# Audio.net
KiCad netlist of a schematic drawn in Altium Designer
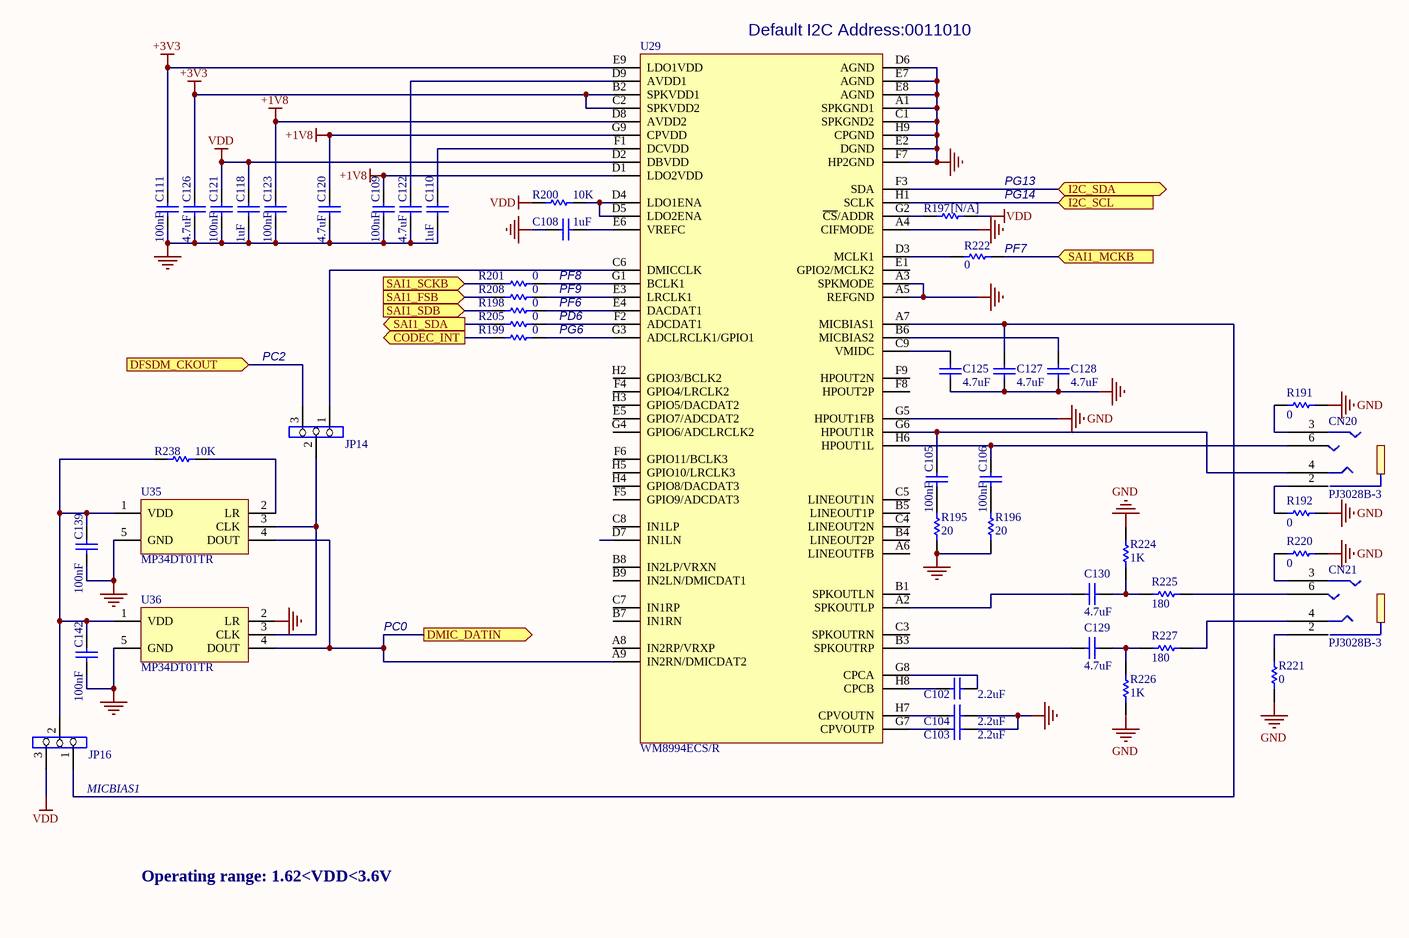
[diagram p0: Audio.SchDoc]

(export (version "E")
  (design (tool "Eeschema 10.0.6"))
  (components
    (comp (ref "C102")
      (value "2.2uF")
      (footprint "0603C")
      (description "Capacitor")
      (fields (field (name "PUBLISHER") "Altium Limited"))
      (libsource (lib "Miscellaneous Devices") (part "CAP"))
    )
    (comp (ref "C103")
      (value "2.2uF")
      (footprint "0603C")
      (description "Capacitor")
      (fields (field (name "PUBLISHER") "Altium Limited"))
      (libsource (lib "Miscellaneous Devices") (part "CAP"))
    )
    (comp (ref "C104")
      (value "2.2uF")
      (footprint "0603C")
      (description "Capacitor")
      (fields (field (name "PUBLISHER") "Altium Limited"))
      (libsource (lib "Miscellaneous Devices") (part "CAP"))
    )
    (comp (ref "C105")
      (value "100nF")
      (footprint "0402C")
      (description "Capacitor")
      (fields (field (name "PUBLISHER") "Altium Limited"))
      (libsource (lib "Miscellaneous Devices") (part "Cap"))
    )
    (comp (ref "C106")
      (value "100nF")
      (footprint "0402C")
      (description "Capacitor")
      (fields (field (name "PUBLISHER") "Altium Limited"))
      (libsource (lib "Miscellaneous Devices") (part "Cap"))
    )
    (comp (ref "C108")
      (value "1uF")
      (footprint "0603C")
      (description "Capacitor")
      (fields (field (name "PUBLISHER") "Altium Limited"))
      (libsource (lib "Miscellaneous Devices") (part "CAP"))
    )
    (comp (ref "C109")
      (value "100nF")
      (footprint "0402C")
      (description "Capacitor")
      (fields (field (name "PUBLISHER") "Altium Limited"))
      (libsource (lib "Miscellaneous Devices") (part "Cap"))
    )
    (comp (ref "C110")
      (value "1uF")
      (footprint "0603C")
      (description "Capacitor")
      (fields (field (name "PUBLISHER") "Altium Limited"))
      (libsource (lib "Miscellaneous Devices") (part "CAP"))
    )
    (comp (ref "C111")
      (value "100nF")
      (footprint "0402C")
      (description "Capacitor")
      (fields (field (name "PUBLISHER") "Altium Limited"))
      (libsource (lib "Miscellaneous Devices") (part "Cap"))
    )
    (comp (ref "C118")
      (value "1uF")
      (footprint "0603C")
      (description "Capacitor")
      (fields (field (name "PUBLISHER") "Altium Limited"))
      (libsource (lib "Miscellaneous Devices") (part "CAP"))
    )
    (comp (ref "C120")
      (value "4.7uF")
      (footprint "0603C")
      (description "Capacitor")
      (fields (field (name "PUBLISHER") "Altium Limited"))
      (libsource (lib "Miscellaneous Devices") (part "Cap"))
    )
    (comp (ref "C121")
      (value "100nF")
      (footprint "0402C")
      (description "Capacitor")
      (fields (field (name "PUBLISHER") "Altium Limited"))
      (libsource (lib "Miscellaneous Devices") (part "Cap"))
    )
    (comp (ref "C122")
      (value "4.7uF")
      (footprint "0603C")
      (description "Capacitor")
      (fields (field (name "PUBLISHER") "Altium Limited"))
      (libsource (lib "Miscellaneous Devices") (part "Cap"))
    )
    (comp (ref "C123")
      (value "100nF")
      (footprint "0402C")
      (description "Capacitor")
      (fields (field (name "PUBLISHER") "Altium Limited"))
      (libsource (lib "Miscellaneous Devices") (part "Cap"))
    )
    (comp (ref "C125")
      (value "4.7uF")
      (footprint "0603C")
      (description "Capacitor")
      (fields (field (name "PUBLISHER") "Altium Limited"))
      (libsource (lib "Miscellaneous Devices") (part "Cap"))
    )
    (comp (ref "C126")
      (value "4.7uF")
      (footprint "0603C")
      (description "Capacitor")
      (fields (field (name "PUBLISHER") "Altium Limited"))
      (libsource (lib "Miscellaneous Devices") (part "Cap"))
    )
    (comp (ref "C127")
      (value "4.7uF")
      (footprint "0603C")
      (description "Capacitor")
      (fields (field (name "PUBLISHER") "Altium Limited"))
      (libsource (lib "Miscellaneous Devices") (part "Cap"))
    )
    (comp (ref "C128")
      (value "4.7uF")
      (footprint "0603C")
      (description "Capacitor")
      (fields (field (name "PUBLISHER") "Altium Limited"))
      (libsource (lib "Miscellaneous Devices") (part "Cap"))
    )
    (comp (ref "C129")
      (value "4.7uF")
      (footprint "0603C")
      (description "Capacitor")
      (fields (field (name "PUBLISHER") "Altium Limited"))
      (libsource (lib "Miscellaneous Devices") (part "Cap"))
    )
    (comp (ref "C130")
      (value "4.7uF")
      (footprint "0603C")
      (description "Capacitor")
      (fields (field (name "PUBLISHER") "Altium Limited"))
      (libsource (lib "Miscellaneous Devices") (part "Cap"))
    )
    (comp (ref "C139")
      (value "100nF")
      (footprint "0402C")
      (description "Capacitor")
      (fields (field (name "PUBLISHER") "Altium Limited"))
      (libsource (lib "Miscellaneous Devices") (part "Cap"))
    )
    (comp (ref "C142")
      (value "100nF")
      (footprint "0402C")
      (description "Capacitor")
      (fields (field (name "PUBLISHER") "Altium Limited"))
      (libsource (lib "Miscellaneous Devices") (part "Cap"))
    )
    (comp (ref "CN20") (value "PJ3028B-3") (footprint "PJ3028B") (libsource (lib "MB786") (part "PJ3028B-3")))
    (comp (ref "CN21") (value "PJ3028B-3") (footprint "PJ3028B") (libsource (lib "MB786") (part "PJ3028B-3")))
    (comp (ref "JP14")
      (value "Header 3X1")
      (footprint "SIP3")
      (libsource (lib "STR910_SCHLIB") (part "Jumper3"))
    )
    (comp (ref "JP16")
      (value "Header 3X1")
      (footprint "SIP3")
      (libsource (lib "STR910_SCHLIB") (part "Jumper3"))
    )
    (comp (ref "R191")
      (value "0")
      (footprint "0603R")
      (description "Resistor")
      (fields (field (name "PUBLISHER") "Altium Limited"))
      (libsource (lib "Miscellaneous Devices") (part "Res1"))
    )
    (comp (ref "R192")
      (value "0")
      (footprint "0603R")
      (description "Resistor")
      (fields (field (name "PUBLISHER") "Altium Limited"))
      (libsource (lib "Miscellaneous Devices") (part "Res1"))
    )
    (comp (ref "R195")
      (value "20")
      (footprint "0402R")
      (description "Resistor")
      (fields (field (name "PUBLISHER") "Altium Limited"))
      (libsource (lib "Miscellaneous Devices") (part "Res1"))
    )
    (comp (ref "R196")
      (value "20")
      (footprint "0402R")
      (description "Resistor")
      (fields (field (name "PUBLISHER") "Altium Limited"))
      (libsource (lib "Miscellaneous Devices") (part "Res1"))
    )
    (comp (ref "R197")
      (value "[N/A]")
      (footprint "0603R")
      (description "Resistor")
      (fields (field (name "PUBLISHER") "Altium Limited"))
      (libsource (lib "Miscellaneous Devices") (part "Res1"))
    )
    (comp (ref "R198")
      (value "0")
      (footprint "0603R")
      (description "Resistor")
      (fields (field (name "PUBLISHER") "Altium Limited"))
      (libsource (lib "Miscellaneous Devices") (part "Res1"))
    )
    (comp (ref "R199")
      (value "0")
      (footprint "0603R")
      (description "Resistor")
      (fields (field (name "PUBLISHER") "Altium Limited"))
      (libsource (lib "Miscellaneous Devices") (part "Res1"))
    )
    (comp (ref "R200")
      (value "10K")
      (footprint "0402R")
      (description "Resistor")
      (fields (field (name "PUBLISHER") "Altium Limited"))
      (libsource (lib "Miscellaneous Devices") (part "Res1"))
    )
    (comp (ref "R201")
      (value "0")
      (footprint "0603R")
      (description "Resistor")
      (fields (field (name "PUBLISHER") "Altium Limited"))
      (libsource (lib "Miscellaneous Devices") (part "Res1"))
    )
    (comp (ref "R205")
      (value "0")
      (footprint "0603R")
      (description "Resistor")
      (fields (field (name "PUBLISHER") "Altium Limited"))
      (libsource (lib "Miscellaneous Devices") (part "Res1"))
    )
    (comp (ref "R208")
      (value "0")
      (footprint "0603R")
      (description "Resistor")
      (fields (field (name "PUBLISHER") "Altium Limited"))
      (libsource (lib "Miscellaneous Devices") (part "Res1"))
    )
    (comp (ref "R220")
      (value "0")
      (footprint "0603R")
      (description "Resistor")
      (fields (field (name "PUBLISHER") "Altium Limited"))
      (libsource (lib "Miscellaneous Devices") (part "Res1"))
    )
    (comp (ref "R221")
      (value "0")
      (footprint "0603R")
      (description "Resistor")
      (fields (field (name "PUBLISHER") "Altium Limited"))
      (libsource (lib "Miscellaneous Devices") (part "Res1"))
    )
    (comp (ref "R222")
      (value "0")
      (footprint "0603R")
      (description "Resistor")
      (fields (field (name "PUBLISHER") "Altium Limited"))
      (libsource (lib "Miscellaneous Devices") (part "Res1"))
    )
    (comp (ref "R224")
      (value "1K")
      (footprint "0402R")
      (description "Resistor")
      (fields (field (name "PUBLISHER") "Altium Limited"))
      (libsource (lib "Miscellaneous Devices") (part "Res1"))
    )
    (comp (ref "R225")
      (value "180")
      (footprint "0402R")
      (description "Resistor")
      (fields (field (name "PUBLISHER") "Altium Limited"))
      (libsource (lib "Miscellaneous Devices") (part "Res1"))
    )
    (comp (ref "R226")
      (value "1K")
      (footprint "0402R")
      (description "Resistor")
      (fields (field (name "PUBLISHER") "Altium Limited"))
      (libsource (lib "Miscellaneous Devices") (part "Res1"))
    )
    (comp (ref "R227")
      (value "180")
      (footprint "0402R")
      (description "Resistor")
      (fields (field (name "PUBLISHER") "Altium Limited"))
      (libsource (lib "Miscellaneous Devices") (part "Res1"))
    )
    (comp (ref "R238")
      (value "10K")
      (footprint "0402R")
      (description "Resistor")
      (fields (field (name "PUBLISHER") "Altium Limited"))
      (libsource (lib "Miscellaneous Devices") (part "Res1"))
    )
    (comp (ref "U29")
      (value "WM8994ECS/R")
      (footprint "BGA72_0R5_4R5X4")
      (libsource (lib "mb1045") (part "WM8994ECS/R"))
    )
    (comp (ref "U35")
      (value "MP34DT01TR")
      (footprint "MP34DT01TR")
      (description "MEMS audio sensor")
      (fields (field (name "PUBLISHER") "Altium Limited"))
      (libsource (lib "mb1045") (part "MP34DT01TR"))
    )
    (comp (ref "U36")
      (value "MP34DT01TR")
      (footprint "MP34DT01TR")
      (description "MEMS audio sensor")
      (fields (field (name "PUBLISHER") "Altium Limited"))
      (libsource (lib "mb1045") (part "MP34DT01TR"))
    )
  )
  (nets
    (net (code "1") (name "+1V8") (class "Default")
      (node (ref "C109") (pin "1") (pinfunction "1_1") (pintype "passive"))
      (node (ref "C120") (pin "1") (pinfunction "1_1") (pintype "passive"))
      (node (ref "C123") (pin "1") (pinfunction "1_1") (pintype "passive"))
      (node (ref "U29") (pin "D1") (pinfunction "LDO2VDD_D1") (pintype "passive"))
      (node (ref "U29") (pin "D8") (pinfunction "AVDD2_D8") (pintype "passive"))
      (node (ref "U29") (pin "G9") (pinfunction "CPVDD_G9") (pintype "passive"))
    )
    (net (code "2") (name "+3V3") (class "Default")
      (node (ref "C111") (pin "1") (pinfunction "1_1") (pintype "passive"))
      (node (ref "C126") (pin "1") (pinfunction "1_1") (pintype "passive"))
      (node (ref "U29") (pin "B2") (pinfunction "SPKVDD1_B2") (pintype "passive"))
      (node (ref "U29") (pin "C2") (pinfunction "SPKVDD2_C2") (pintype "passive"))
      (node (ref "U29") (pin "E9") (pinfunction "LDO1VDD_E9") (pintype "passive"))
    )
    (net (code "3") (name "/CODEC_INT") (class "Default")
      (node (ref "R199") (pin "2") (pinfunction "2_2") (pintype "passive"))
    )
    (net (code "4") (name "/DFSDM_CKOUT") (class "Default") (node (ref "JP14") (pin "3") (pintype "passive")))
    (net (code "5") (name "/DMIC_DATIN") (class "Default")
      (node (ref "U29") (pin "A9") (pinfunction "IN2RN/DMICDAT2_A9") (pintype "passive"))
      (node (ref "U35") (pin "4") (pinfunction "DOUT_4") (pintype "passive"))
      (node (ref "U36") (pin "4") (pinfunction "DOUT_4") (pintype "passive"))
    )
    (net (code "6") (name "/I2C_SCL") (class "Default")
      (node (ref "U29") (pin "H1") (pinfunction "SCLK_H1") (pintype "passive"))
    )
    (net (code "7") (name "/I2C_SDA") (class "Default")
      (node (ref "U29") (pin "F3") (pinfunction "SDA_F3") (pintype "passive"))
    )
    (net (code "8") (name "/SAI1_FSB") (class "Default")
      (node (ref "R208") (pin "2") (pinfunction "2_2") (pintype "passive"))
    )
    (net (code "9") (name "/SAI1_MCKB") (class "Default")
      (node (ref "R222") (pin "1") (pinfunction "1_1") (pintype "passive"))
    )
    (net (code "10") (name "/SAI1_SCKB") (class "Default")
      (node (ref "R201") (pin "2") (pinfunction "2_2") (pintype "passive"))
    )
    (net (code "11") (name "/SAI1_SDA") (class "Default")
      (node (ref "R205") (pin "2") (pinfunction "2_2") (pintype "passive"))
    )
    (net (code "12") (name "/SAI1_SDB") (class "Default")
      (node (ref "R198") (pin "2") (pinfunction "2_2") (pintype "passive"))
    )
    (net (code "13") (name "GND") (class "Default")
      (node (ref "C103") (pin "2") (pinfunction "2_2") (pintype "passive"))
      (node (ref "C104") (pin "2") (pinfunction "2_2") (pintype "passive"))
      (node (ref "C108") (pin "2") (pinfunction "2_2") (pintype "passive"))
      (node (ref "C109") (pin "2") (pinfunction "2_2") (pintype "passive"))
      (node (ref "C110") (pin "2") (pinfunction "2_2") (pintype "passive"))
      (node (ref "C111") (pin "2") (pinfunction "2_2") (pintype "passive"))
      (node (ref "C118") (pin "2") (pinfunction "2_2") (pintype "passive"))
      (node (ref "C120") (pin "2") (pinfunction "2_2") (pintype "passive"))
      (node (ref "C121") (pin "2") (pinfunction "2_2") (pintype "passive"))
      (node (ref "C122") (pin "2") (pinfunction "2_2") (pintype "passive"))
      (node (ref "C123") (pin "2") (pinfunction "2_2") (pintype "passive"))
      (node (ref "C125") (pin "1") (pinfunction "1_1") (pintype "passive"))
      (node (ref "C126") (pin "2") (pinfunction "2_2") (pintype "passive"))
      (node (ref "C127") (pin "1") (pinfunction "1_1") (pintype "passive"))
      (node (ref "C128") (pin "1") (pinfunction "1_1") (pintype "passive"))
      (node (ref "C139") (pin "2") (pinfunction "2_2") (pintype "passive"))
      (node (ref "C142") (pin "2") (pinfunction "2_2") (pintype "passive"))
      (node (ref "R191") (pin "2") (pinfunction "2_2") (pintype "passive"))
      (node (ref "R192") (pin "1") (pinfunction "1_1") (pintype "passive"))
      (node (ref "R195") (pin "2") (pinfunction "2_2") (pintype "passive"))
      (node (ref "R196") (pin "2") (pinfunction "2_2") (pintype "passive"))
      (node (ref "R220") (pin "2") (pinfunction "2_2") (pintype "passive"))
      (node (ref "R221") (pin "2") (pinfunction "2_2") (pintype "passive"))
      (node (ref "R224") (pin "1") (pinfunction "1_1") (pintype "passive"))
      (node (ref "R226") (pin "1") (pinfunction "1_1") (pintype "passive"))
      (node (ref "U29") (pin "A1") (pinfunction "SPKGND1_A1") (pintype "passive"))
      (node (ref "U29") (pin "A3") (pinfunction "SPKMODE_A3") (pintype "passive"))
      (node (ref "U29") (pin "A4") (pinfunction "CIFMODE_A4") (pintype "passive"))
      (node (ref "U29") (pin "A5") (pinfunction "REFGND_A5") (pintype "passive"))
      (node (ref "U29") (pin "C1") (pinfunction "SPKGND2_C1") (pintype "passive"))
      (node (ref "U29") (pin "D6") (pinfunction "AGND_D6") (pintype "passive"))
      (node (ref "U29") (pin "E2") (pinfunction "DGND_E2") (pintype "passive"))
      (node (ref "U29") (pin "E7") (pinfunction "AGND_E7") (pintype "passive"))
      (node (ref "U29") (pin "E8") (pinfunction "AGND_E8") (pintype "passive"))
      (node (ref "U29") (pin "F7") (pinfunction "HP2GND_F7") (pintype "passive"))
      (node (ref "U29") (pin "G5") (pinfunction "HPOUT1FB_G5") (pintype "passive"))
      (node (ref "U29") (pin "H9") (pinfunction "CPGND_H9") (pintype "passive"))
      (node (ref "U35") (pin "5") (pinfunction "GND_5") (pintype "passive"))
      (node (ref "U36") (pin "2") (pinfunction "LR_2") (pintype "passive"))
      (node (ref "U36") (pin "5") (pinfunction "GND_5") (pintype "passive"))
    )
    (net (code "14") (name "Net-(C105-Pad2)") (class "Default")
      (node (ref "C105") (pin "2") (pinfunction "2_2") (pintype "passive"))
      (node (ref "R195") (pin "1") (pinfunction "1_1") (pintype "passive"))
    )
    (net (code "15") (name "Net-(C106-Pad2)") (class "Default")
      (node (ref "C106") (pin "2") (pinfunction "2_2") (pintype "passive"))
      (node (ref "R196") (pin "1") (pinfunction "1_1") (pintype "passive"))
    )
    (net (code "16") (name "Net-(C129-Pad1)") (class "Default")
      (node (ref "C129") (pin "1") (pinfunction "1_1") (pintype "passive"))
      (node (ref "R226") (pin "2") (pinfunction "2_2") (pintype "passive"))
      (node (ref "R227") (pin "2") (pinfunction "2_2") (pintype "passive"))
    )
    (net (code "17") (name "Net-(C130-Pad1)") (class "Default")
      (node (ref "C130") (pin "1") (pinfunction "1_1") (pintype "passive"))
      (node (ref "R224") (pin "2") (pinfunction "2_2") (pintype "passive"))
      (node (ref "R225") (pin "1") (pinfunction "1_1") (pintype "passive"))
    )
    (net (code "18") (name "Net-(CN20-Pad2)") (class "Default")
      (node (ref "CN20") (pin "2") (pintype "passive"))
      (node (ref "R192") (pin "2") (pinfunction "2_2") (pintype "passive"))
    )
    (net (code "19") (name "Net-(CN20-Pad3)") (class "Default")
      (node (ref "CN20") (pin "3") (pintype "passive"))
      (node (ref "R191") (pin "1") (pinfunction "1_1") (pintype "passive"))
    )
    (net (code "20") (name "Net-(CN21-Pad2)") (class "Default")
      (node (ref "CN21") (pin "2") (pintype "passive"))
      (node (ref "R221") (pin "1") (pinfunction "1_1") (pintype "passive"))
    )
    (net (code "21") (name "Net-(CN21-Pad3)") (class "Default")
      (node (ref "CN21") (pin "3") (pintype "passive"))
      (node (ref "R220") (pin "1") (pinfunction "1_1") (pintype "passive"))
    )
    (net (code "22") (name "Net-(CN21-Pad4)") (class "Default")
      (node (ref "CN21") (pin "4") (pintype "passive"))
      (node (ref "R227") (pin "1") (pinfunction "1_1") (pintype "passive"))
    )
    (net (code "23") (name "Net-(CN21-Pad6)") (class "Default")
      (node (ref "CN21") (pin "6") (pintype "passive"))
      (node (ref "R225") (pin "2") (pinfunction "2_2") (pintype "passive"))
    )
    (net (code "24") (name "Net-(U29-ADCDAT1)") (class "Default")
      (node (ref "R205") (pin "1") (pinfunction "1_1") (pintype "passive"))
      (node (ref "U29") (pin "F2") (pinfunction "ADCDAT1_F2") (pintype "passive"))
    )
    (net (code "25") (name "Net-(U29-ADCLRCLK1{slash}GPIO1)") (class "Default")
      (node (ref "R199") (pin "1") (pinfunction "1_1") (pintype "passive"))
      (node (ref "U29") (pin "G3") (pinfunction "ADCLRCLK1/GPIO1_G3") (pintype "passive"))
    )
    (net (code "26") (name "Net-(U29-AVDD1)") (class "Default")
      (node (ref "C122") (pin "1") (pinfunction "1_1") (pintype "passive"))
      (node (ref "U29") (pin "D9") (pinfunction "AVDD1_D9") (pintype "passive"))
    )
    (net (code "27") (name "Net-(U29-BCLK1)") (class "Default")
      (node (ref "R201") (pin "1") (pinfunction "1_1") (pintype "passive"))
      (node (ref "U29") (pin "G1") (pinfunction "BCLK1_G1") (pintype "passive"))
    )
    (net (code "28") (name "Net-(U29-CPCA)") (class "Default")
      (node (ref "C102") (pin "2") (pinfunction "2_2") (pintype "passive"))
      (node (ref "U29") (pin "G8") (pinfunction "CPCA_G8") (pintype "passive"))
    )
    (net (code "29") (name "Net-(U29-CPCB)") (class "Default")
      (node (ref "C102") (pin "1") (pinfunction "1_1") (pintype "passive"))
      (node (ref "U29") (pin "H8") (pinfunction "CPCB_H8") (pintype "passive"))
    )
    (net (code "30") (name "Net-(U29-CPVOUTN)") (class "Default")
      (node (ref "C104") (pin "1") (pinfunction "1_1") (pintype "passive"))
      (node (ref "U29") (pin "H7") (pinfunction "CPVOUTN_H7") (pintype "passive"))
    )
    (net (code "31") (name "Net-(U29-CPVOUTP)") (class "Default")
      (node (ref "C103") (pin "1") (pinfunction "1_1") (pintype "passive"))
      (node (ref "U29") (pin "G7") (pinfunction "CPVOUTP_G7") (pintype "passive"))
    )
    (net (code "32") (name "Net-(U29-DACDAT1)") (class "Default")
      (node (ref "R198") (pin "1") (pinfunction "1_1") (pintype "passive"))
      (node (ref "U29") (pin "E4") (pinfunction "DACDAT1_E4") (pintype "passive"))
    )
    (net (code "33") (name "Net-(U29-DCVDD)") (class "Default")
      (node (ref "C110") (pin "1") (pinfunction "1_1") (pintype "passive"))
      (node (ref "U29") (pin "F1") (pinfunction "DCVDD_F1") (pintype "passive"))
    )
    (net (code "34") (name "Net-(U29-DMICCLK)") (class "Default")
      (node (ref "JP14") (pin "1") (pintype "passive"))
      (node (ref "U29") (pin "C6") (pinfunction "DMICCLK_C6") (pintype "passive"))
    )
    (net (code "35") (name "Net-(U29-HPOUT1L)") (class "Default")
      (node (ref "C106") (pin "1") (pinfunction "1_1") (pintype "passive"))
      (node (ref "CN20") (pin "6") (pintype "passive"))
      (node (ref "U29") (pin "H6") (pinfunction "HPOUT1L_H6") (pintype "passive"))
    )
    (net (code "36") (name "Net-(U29-HPOUT1R)") (class "Default")
      (node (ref "C105") (pin "1") (pinfunction "1_1") (pintype "passive"))
      (node (ref "CN20") (pin "4") (pintype "passive"))
      (node (ref "U29") (pin "G6") (pinfunction "HPOUT1R_G6") (pintype "passive"))
    )
    (net (code "37") (name "Net-(U29-LDO1ENA)") (class "Default")
      (node (ref "R200") (pin "1") (pinfunction "1_1") (pintype "passive"))
      (node (ref "U29") (pin "D4") (pinfunction "LDO1ENA_D4") (pintype "passive"))
      (node (ref "U29") (pin "D5") (pinfunction "LDO2ENA_D5") (pintype "passive"))
    )
    (net (code "38") (name "Net-(U29-LRCLK1)") (class "Default")
      (node (ref "R208") (pin "1") (pinfunction "1_1") (pintype "passive"))
      (node (ref "U29") (pin "E3") (pinfunction "LRCLK1_E3") (pintype "passive"))
    )
    (net (code "39") (name "Net-(U29-MCLK1)") (class "Default")
      (node (ref "R222") (pin "2") (pinfunction "2_2") (pintype "passive"))
      (node (ref "U29") (pin "D3") (pinfunction "MCLK1_D3") (pintype "passive"))
    )
    (net (code "40") (name "Net-(U29-MICBIAS1)") (class "Default")
      (node (ref "C127") (pin "2") (pinfunction "2_2") (pintype "passive"))
      (node (ref "JP16") (pin "1") (pintype "passive"))
      (node (ref "U29") (pin "A7") (pinfunction "MICBIAS1_A7") (pintype "passive"))
    )
    (net (code "41") (name "Net-(U29-MICBIAS2)") (class "Default")
      (node (ref "C128") (pin "2") (pinfunction "2_2") (pintype "passive"))
      (node (ref "U29") (pin "B6") (pinfunction "MICBIAS2_B6") (pintype "passive"))
    )
    (net (code "42") (name "Net-(U29-SPKOUTLP)") (class "Default")
      (node (ref "C130") (pin "2") (pinfunction "2_2") (pintype "passive"))
      (node (ref "U29") (pin "A2") (pinfunction "SPKOUTLP_A2") (pintype "passive"))
    )
    (net (code "43") (name "Net-(U29-SPKOUTRP)") (class "Default")
      (node (ref "C129") (pin "2") (pinfunction "2_2") (pintype "passive"))
      (node (ref "U29") (pin "B3") (pinfunction "SPKOUTRP_B3") (pintype "passive"))
    )
    (net (code "44") (name "Net-(U29-VMIDC)") (class "Default")
      (node (ref "C125") (pin "2") (pinfunction "2_2") (pintype "passive"))
      (node (ref "U29") (pin "C9") (pinfunction "VMIDC_C9") (pintype "passive"))
    )
    (net (code "45") (name "Net-(U29-VREFC)") (class "Default")
      (node (ref "C108") (pin "1") (pinfunction "1_1") (pintype "passive"))
      (node (ref "U29") (pin "E6") (pinfunction "VREFC_E6") (pintype "passive"))
    )
    (net (code "46") (name "Net-(U29-~{CS}{slash}ADDR)") (class "Default")
      (node (ref "R197") (pin "2") (pinfunction "2_2") (pintype "passive"))
      (node (ref "U29") (pin "G2") (pinfunction "~{CS}/ADDR_G2") (pintype "passive"))
    )
    (net (code "47") (name "Net-(U35-CLK)") (class "Default")
      (node (ref "JP14") (pin "2") (pintype "passive"))
      (node (ref "U35") (pin "3") (pinfunction "CLK_3") (pintype "passive"))
      (node (ref "U36") (pin "3") (pinfunction "CLK_3") (pintype "passive"))
    )
    (net (code "48") (name "Net-(U35-LR)") (class "Default")
      (node (ref "R238") (pin "1") (pinfunction "1_1") (pintype "passive"))
      (node (ref "U35") (pin "2") (pinfunction "LR_2") (pintype "passive"))
    )
    (net (code "49") (name "Net-(U35-VDD)") (class "Default")
      (node (ref "C139") (pin "1") (pinfunction "1_1") (pintype "passive"))
      (node (ref "C142") (pin "1") (pinfunction "1_1") (pintype "passive"))
      (node (ref "JP16") (pin "2") (pintype "passive"))
      (node (ref "R238") (pin "2") (pinfunction "2_2") (pintype "passive"))
      (node (ref "U35") (pin "1") (pinfunction "VDD_1") (pintype "passive"))
      (node (ref "U36") (pin "1") (pinfunction "VDD_1") (pintype "passive"))
    )
    (net (code "50") (name "VDD") (class "Default")
      (node (ref "C118") (pin "1") (pinfunction "1_1") (pintype "passive"))
      (node (ref "C121") (pin "1") (pinfunction "1_1") (pintype "passive"))
      (node (ref "JP16") (pin "3") (pintype "passive"))
      (node (ref "R197") (pin "1") (pinfunction "1_1") (pintype "passive"))
      (node (ref "R200") (pin "2") (pinfunction "2_2") (pintype "passive"))
      (node (ref "U29") (pin "D2") (pinfunction "DBVDD_D2") (pintype "passive"))
    )
    (net (code "51") (name "unconnected-(U29-GPIO2{slash}MCLK2-PadE1)") (class "Default")
      (node (ref "U29") (pin "E1") (pinfunction "GPIO2/MCLK2_E1") (pintype "passive"))
    )
    (net (code "52") (name "unconnected-(U29-GPIO3{slash}BCLK2-PadH2)") (class "Default")
      (node (ref "U29") (pin "H2") (pinfunction "GPIO3/BCLK2_H2") (pintype "passive"))
    )
    (net (code "53") (name "unconnected-(U29-GPIO4{slash}LRCLK2-PadF4)") (class "Default")
      (node (ref "U29") (pin "F4") (pinfunction "GPIO4/LRCLK2_F4") (pintype "passive"))
    )
    (net (code "54") (name "unconnected-(U29-GPIO5{slash}DACDAT2-PadH3)") (class "Default")
      (node (ref "U29") (pin "H3") (pinfunction "GPIO5/DACDAT2_H3") (pintype "passive"))
    )
    (net (code "55") (name "unconnected-(U29-GPIO6{slash}ADCLRCLK2-PadG4)") (class "Default")
      (node (ref "U29") (pin "G4") (pinfunction "GPIO6/ADCLRCLK2_G4") (pintype "passive"))
    )
    (net (code "56") (name "unconnected-(U29-GPIO7{slash}ADCDAT2-PadE5)") (class "Default")
      (node (ref "U29") (pin "E5") (pinfunction "GPIO7/ADCDAT2_E5") (pintype "passive"))
    )
    (net (code "57") (name "unconnected-(U29-GPIO8{slash}DACDAT3-PadH4)") (class "Default")
      (node (ref "U29") (pin "H4") (pinfunction "GPIO8/DACDAT3_H4") (pintype "passive"))
    )
    (net (code "58") (name "unconnected-(U29-GPIO9{slash}ADCDAT3-PadF5)") (class "Default")
      (node (ref "U29") (pin "F5") (pinfunction "GPIO9/ADCDAT3_F5") (pintype "passive"))
    )
    (net (code "59") (name "unconnected-(U29-GPIO10{slash}LRCLK3-PadH5)") (class "Default")
      (node (ref "U29") (pin "H5") (pinfunction "GPIO10/LRCLK3_H5") (pintype "passive"))
    )
    (net (code "60") (name "unconnected-(U29-GPIO11{slash}BCLK3-PadF6)") (class "Default")
      (node (ref "U29") (pin "F6") (pinfunction "GPIO11/BCLK3_F6") (pintype "passive"))
    )
    (net (code "61") (name "unconnected-(U29-HPOUT2N-PadF9)") (class "Default")
      (node (ref "U29") (pin "F9") (pinfunction "HPOUT2N_F9") (pintype "passive"))
    )
    (net (code "62") (name "unconnected-(U29-HPOUT2P-PadF8)") (class "Default")
      (node (ref "U29") (pin "F8") (pinfunction "HPOUT2P_F8") (pintype "passive"))
    )
    (net (code "63") (name "unconnected-(U29-IN1LN-PadD7)") (class "Default")
      (node (ref "U29") (pin "D7") (pinfunction "IN1LN_D7") (pintype "passive"))
    )
    (net (code "64") (name "unconnected-(U29-IN1LP-PadC8)") (class "Default")
      (node (ref "U29") (pin "C8") (pinfunction "IN1LP_C8") (pintype "passive"))
    )
    (net (code "65") (name "unconnected-(U29-IN1RN-PadB7)") (class "Default")
      (node (ref "U29") (pin "B7") (pinfunction "IN1RN_B7") (pintype "passive"))
    )
    (net (code "66") (name "unconnected-(U29-IN1RP-PadC7)") (class "Default")
      (node (ref "U29") (pin "C7") (pinfunction "IN1RP_C7") (pintype "passive"))
    )
    (net (code "67") (name "unconnected-(U29-IN2LN{slash}DMICDAT1-PadB9)") (class "Default")
      (node (ref "U29") (pin "B9") (pinfunction "IN2LN/DMICDAT1_B9") (pintype "passive"))
    )
    (net (code "68") (name "unconnected-(U29-IN2LP{slash}VRXN-PadB8)") (class "Default")
      (node (ref "U29") (pin "B8") (pinfunction "IN2LP/VRXN_B8") (pintype "passive"))
    )
    (net (code "69") (name "unconnected-(U29-IN2RP{slash}VRXP-PadA8)") (class "Default")
      (node (ref "U29") (pin "A8") (pinfunction "IN2RP/VRXP_A8") (pintype "passive"))
    )
    (net (code "70") (name "unconnected-(U29-LINEOUT1N-PadC5)") (class "Default")
      (node (ref "U29") (pin "C5") (pinfunction "LINEOUT1N_C5") (pintype "passive"))
    )
    (net (code "71") (name "unconnected-(U29-LINEOUT1P-PadB5)") (class "Default")
      (node (ref "U29") (pin "B5") (pinfunction "LINEOUT1P_B5") (pintype "passive"))
    )
    (net (code "72") (name "unconnected-(U29-LINEOUT2N-PadC4)") (class "Default")
      (node (ref "U29") (pin "C4") (pinfunction "LINEOUT2N_C4") (pintype "passive"))
    )
    (net (code "73") (name "unconnected-(U29-LINEOUT2P-PadB4)") (class "Default")
      (node (ref "U29") (pin "B4") (pinfunction "LINEOUT2P_B4") (pintype "passive"))
    )
    (net (code "74") (name "unconnected-(U29-LINEOUTFB-PadA6)") (class "Default")
      (node (ref "U29") (pin "A6") (pinfunction "LINEOUTFB_A6") (pintype "passive"))
    )
    (net (code "75") (name "unconnected-(U29-SPKOUTLN-PadB1)") (class "Default")
      (node (ref "U29") (pin "B1") (pinfunction "SPKOUTLN_B1") (pintype "passive"))
    )
    (net (code "76") (name "unconnected-(U29-SPKOUTRN-PadC3)") (class "Default")
      (node (ref "U29") (pin "C3") (pinfunction "SPKOUTRN_C3") (pintype "passive"))
    )
  )
)
